# trainiii_battery.net
KiCad netlist of a schematic drawn in EAGLE
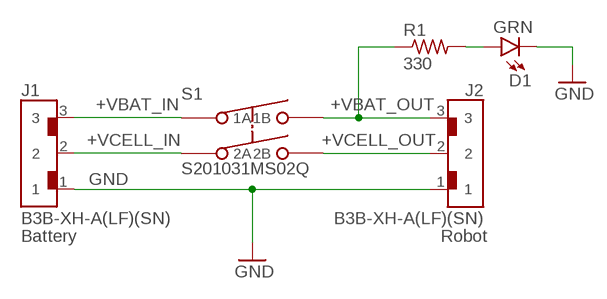
[diagram p0: schematic, sheet 1]

(export (version "E")
  (design (tool "Eeschema 10.0.6"))
  (components
    (comp (ref "D1")
      (value "GRN")
      (footprint "eagle-import:LED-0603")
      (libsource (lib "eagle-import") (part "LED0603"))
    )
    (comp (ref "J1")
      (value "B3B-XH-A(LF)(SN)")
      (footprint "eagle-import:B3B-XH-A(LF)(SN)")
      (libsource (lib "eagle-import") (part "B3B-XH-A(LF)(SN)"))
    )
    (comp (ref "J2")
      (value "B3B-XH-A(LF)(SN)")
      (footprint "eagle-import:B3B-XH-A(LF)(SN)")
      (libsource (lib "eagle-import") (part "B3B-XH-A(LF)(SN)"))
    )
    (comp (ref "R1")
      (value "330")
      (footprint "eagle-import:R0603")
      (libsource (lib "eagle-import") (part "R-US_R0603"))
    )
    (comp (ref "S1")
      (value "S201031MS02Q")
      (footprint "eagle-import:S201")
      (libsource (lib "eagle-import") (part "S201031MS02Q"))
    )
  )
  (nets
    (net (code "1") (name "/+VBAT_IN") (class "Default")
      (node (ref "J1") (pin "3") (pinfunction "3_3") (pintype "bidirectional"))
      (node (ref "S1") (pin "1") (pinfunction "1A_1") (pintype "input"))
    )
    (net (code "2") (name "/+VBAT_OUT") (class "Default")
      (node (ref "J2") (pin "3") (pinfunction "3_3") (pintype "bidirectional"))
      (node (ref "R1") (pin "1") (pinfunction "1_1") (pintype "passive"))
      (node (ref "S1") (pin "2") (pinfunction "1B_2") (pintype "output"))
    )
    (net (code "3") (name "/+VCELL_IN") (class "Default")
      (node (ref "J1") (pin "2") (pinfunction "2_2") (pintype "bidirectional"))
      (node (ref "S1") (pin "4") (pinfunction "2A_4") (pintype "input"))
    )
    (net (code "4") (name "/+VCELL_OUT") (class "Default")
      (node (ref "J2") (pin "2") (pinfunction "2_2") (pintype "bidirectional"))
      (node (ref "S1") (pin "5") (pinfunction "2B_5") (pintype "output"))
    )
    (net (code "5") (name "GND") (class "Default")
      (node (ref "D1") (pin "C") (pinfunction "C_C") (pintype "passive"))
      (node (ref "J1") (pin "1") (pinfunction "1_1") (pintype "bidirectional"))
      (node (ref "J2") (pin "1") (pinfunction "1_1") (pintype "bidirectional"))
    )
    (net (code "6") (name "Net-(D1-PadA)") (class "Default")
      (node (ref "D1") (pin "A") (pinfunction "A_A") (pintype "passive"))
      (node (ref "R1") (pin "2") (pinfunction "2_2") (pintype "passive"))
    )
  )
)
